# Sheet1.net
KiCad netlist of a schematic drawn in Altium Designer
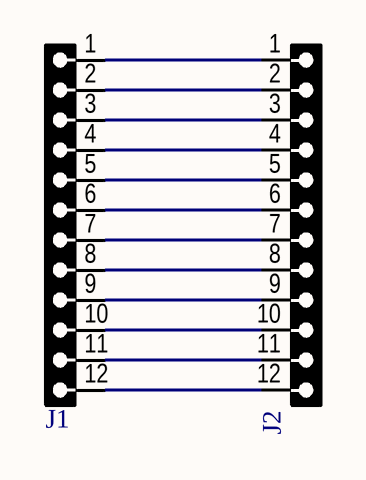
[diagram p0: Sheet1.SchDoc]

(export (version "E")
  (design (tool "Eeschema 10.0.6"))
  (components
    (comp (ref "J1")
      (value "HDRF12")
      (footprint "HDRRS_F_1X9")
      (description "CONN, HEADER, Female, pitch: 2.54mm, 12POS")
      (libsource (lib "Headers") (part "Header Female 1x12 THT"))
    )
    (comp (ref "J2")
      (value "HDRF12")
      (footprint "HDR_F_1X12")
      (description "CONN, HEADER, Female, pitch: 2.54mm, 12POS")
      (libsource (lib "") (part "Header Female 1x12 THT_1"))
    )
  )
  (nets
    (net (code "1") (name "Net-(J1-Pad1)") (class "Default")
      (node (ref "J1") (pin "1") (pinfunction "1_1") (pintype "passive"))
      (node (ref "J2") (pin "1") (pinfunction "1_1") (pintype "passive"))
    )
    (net (code "2") (name "Net-(J1-Pad2)") (class "Default")
      (node (ref "J1") (pin "2") (pinfunction "2_2") (pintype "passive"))
      (node (ref "J2") (pin "2") (pinfunction "2_2") (pintype "passive"))
    )
    (net (code "3") (name "Net-(J1-Pad3)") (class "Default")
      (node (ref "J1") (pin "3") (pinfunction "3_3") (pintype "passive"))
      (node (ref "J2") (pin "3") (pinfunction "3_3") (pintype "passive"))
    )
    (net (code "4") (name "Net-(J1-Pad4)") (class "Default")
      (node (ref "J1") (pin "4") (pinfunction "4_4") (pintype "passive"))
      (node (ref "J2") (pin "4") (pinfunction "4_4") (pintype "passive"))
    )
    (net (code "5") (name "Net-(J1-Pad5)") (class "Default")
      (node (ref "J1") (pin "5") (pinfunction "5_5") (pintype "passive"))
      (node (ref "J2") (pin "5") (pinfunction "5_5") (pintype "passive"))
    )
    (net (code "6") (name "Net-(J1-Pad6)") (class "Default")
      (node (ref "J1") (pin "6") (pinfunction "6_6") (pintype "passive"))
      (node (ref "J2") (pin "6") (pinfunction "6_6") (pintype "passive"))
    )
    (net (code "7") (name "Net-(J1-Pad7)") (class "Default")
      (node (ref "J1") (pin "7") (pinfunction "7_7") (pintype "passive"))
      (node (ref "J2") (pin "7") (pinfunction "7_7") (pintype "passive"))
    )
    (net (code "8") (name "Net-(J1-Pad8)") (class "Default")
      (node (ref "J1") (pin "8") (pinfunction "8_8") (pintype "passive"))
      (node (ref "J2") (pin "8") (pinfunction "8_8") (pintype "passive"))
    )
    (net (code "9") (name "Net-(J1-Pad9)") (class "Default")
      (node (ref "J1") (pin "9") (pinfunction "9_9") (pintype "passive"))
      (node (ref "J2") (pin "9") (pinfunction "9_9") (pintype "passive"))
    )
    (net (code "10") (name "Net-(J1-Pad10)") (class "Default")
      (node (ref "J1") (pin "10") (pinfunction "10_10") (pintype "passive"))
      (node (ref "J2") (pin "10") (pinfunction "10_10") (pintype "passive"))
    )
    (net (code "11") (name "Net-(J1-Pad11)") (class "Default")
      (node (ref "J1") (pin "11") (pinfunction "11_11") (pintype "passive"))
      (node (ref "J2") (pin "11") (pinfunction "11_11") (pintype "passive"))
    )
    (net (code "12") (name "Net-(J1-Pad12)") (class "Default")
      (node (ref "J1") (pin "12") (pinfunction "12_12") (pintype "passive"))
      (node (ref "J2") (pin "12") (pinfunction "12_12") (pintype "passive"))
    )
  )
)
